# Sunsensors_v1_0.net
KiCad netlist of a schematic drawn in EAGLE
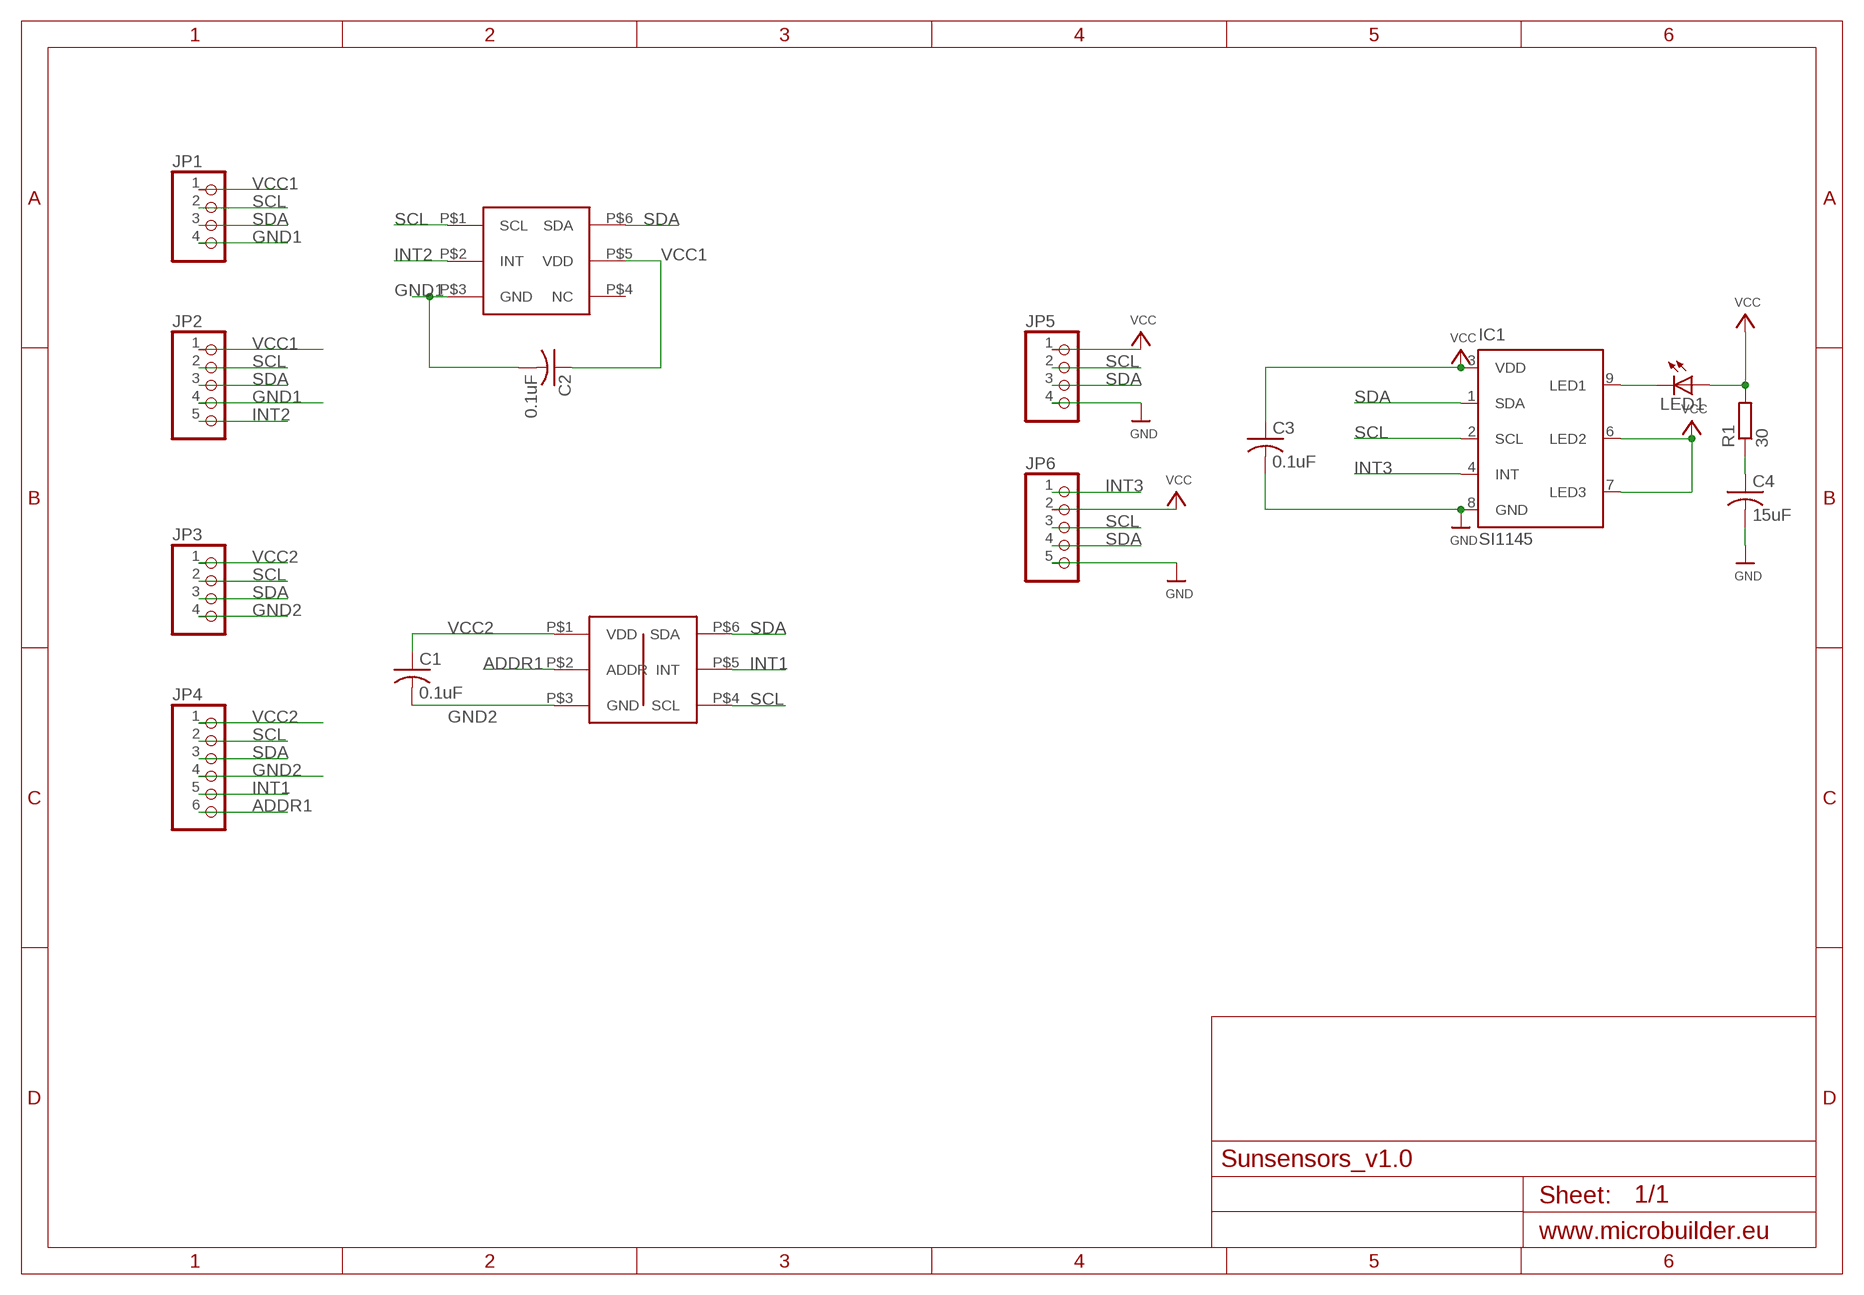
[diagram p0: schematic, sheet 1]

(export (version "E")
  (design (tool "Eeschema 10.0.6"))
  (components
    (comp (ref "C1")
      (value "0.1uF")
      (footprint "eagle-import:C0805")
      (libsource (lib "eagle-import") (part "C-USC0805"))
    )
    (comp (ref "C2")
      (value "0.1uF")
      (footprint "eagle-import:C0805")
      (libsource (lib "eagle-import") (part "C-USC0805"))
    )
    (comp (ref "C3")
      (value "0.1uF")
      (footprint "eagle-import:C0805")
      (libsource (lib "eagle-import") (part "C-USC0805"))
    )
    (comp (ref "C4")
      (value "15uF")
      (footprint "eagle-import:C0805")
      (libsource (lib "eagle-import") (part "C-USC0805"))
    )
    (comp (ref "IC1")
      (value "SI1145")
      (footprint "eagle-import:QFN-10")
      (libsource (lib "eagle-import") (part "SI1145"))
    )
    (comp (ref "JP1")
      (value "PINHD-1X4")
      (footprint "eagle-import:1X04")
      (libsource (lib "eagle-import") (part "PINHD-1X4"))
    )
    (comp (ref "JP2")
      (value "PINHD-1X5")
      (footprint "eagle-import:1X05")
      (libsource (lib "eagle-import") (part "PINHD-1X5"))
    )
    (comp (ref "JP3")
      (value "PINHD-1X4")
      (footprint "eagle-import:1X04")
      (libsource (lib "eagle-import") (part "PINHD-1X4"))
    )
    (comp (ref "JP4")
      (value "PINHD-1X6")
      (footprint "eagle-import:1X06")
      (libsource (lib "eagle-import") (part "PINHD-1X6"))
    )
    (comp (ref "JP5")
      (value "PINHD-1X4")
      (footprint "eagle-import:1X04")
      (libsource (lib "eagle-import") (part "PINHD-1X4"))
    )
    (comp (ref "JP6")
      (value "PINHD-1X5")
      (footprint "eagle-import:1X05")
      (libsource (lib "eagle-import") (part "PINHD-1X5"))
    )
    (comp (ref "LED1")
      (value "LEDCHIPLED_0805")
      (footprint "eagle-import:CHIPLED_0805")
      (libsource (lib "eagle-import") (part "LEDCHIPLED_0805"))
    )
    (comp (ref "R1")
      (value "30")
      (footprint "eagle-import:R1206")
      (libsource (lib "eagle-import") (part "R-EU_R1206"))
    )
    (comp (ref "U$8")
      (value "TSL25911FN")
      (footprint "eagle-import:ODFN6")
      (libsource (lib "eagle-import") (part "TSL25911FN"))
    )
    (comp (ref "U$9")
      (value "TSL2561T")
      (footprint "eagle-import:TMB-6")
      (libsource (lib "eagle-import") (part "TSL2561T"))
    )
  )
  (nets
    (net (code "1") (name "/ADDR1") (class "Default")
      (node (ref "JP4") (pin "6") (pinfunction "6_6") (pintype "passive"))
      (node (ref "U$9") (pin "P$2") (pinfunction "ADDR_P$2") (pintype "bidirectional"))
    )
    (net (code "2") (name "/GND1") (class "Default")
      (node (ref "C2") (pin "2") (pinfunction "2_2") (pintype "passive"))
      (node (ref "JP1") (pin "4") (pinfunction "4_4") (pintype "passive"))
      (node (ref "JP2") (pin "4") (pinfunction "4_4") (pintype "passive"))
      (node (ref "U$8") (pin "P$3") (pinfunction "GND_P$3") (pintype "bidirectional"))
    )
    (net (code "3") (name "/GND2") (class "Default")
      (node (ref "C1") (pin "2") (pinfunction "2_2") (pintype "passive"))
      (node (ref "JP3") (pin "4") (pinfunction "4_4") (pintype "passive"))
      (node (ref "JP4") (pin "4") (pinfunction "4_4") (pintype "passive"))
      (node (ref "U$9") (pin "P$3") (pinfunction "GND_P$3") (pintype "bidirectional"))
    )
    (net (code "4") (name "/INT1") (class "Default")
      (node (ref "JP4") (pin "5") (pinfunction "5_5") (pintype "passive"))
      (node (ref "U$9") (pin "P$5") (pinfunction "INT_P$5") (pintype "bidirectional"))
    )
    (net (code "5") (name "/INT2") (class "Default")
      (node (ref "JP2") (pin "5") (pinfunction "5_5") (pintype "passive"))
      (node (ref "U$8") (pin "P$2") (pinfunction "INT_P$2") (pintype "bidirectional"))
    )
    (net (code "6") (name "/INT3") (class "Default")
      (node (ref "IC1") (pin "4") (pinfunction "INT_4") (pintype "open_collector"))
      (node (ref "JP6") (pin "1") (pinfunction "1_1") (pintype "passive"))
    )
    (net (code "7") (name "/SCL") (class "Default")
      (node (ref "IC1") (pin "2") (pinfunction "SCL_2") (pintype "input"))
      (node (ref "JP1") (pin "2") (pinfunction "2_2") (pintype "passive"))
      (node (ref "JP2") (pin "2") (pinfunction "2_2") (pintype "passive"))
      (node (ref "JP3") (pin "2") (pinfunction "2_2") (pintype "passive"))
      (node (ref "JP4") (pin "2") (pinfunction "2_2") (pintype "passive"))
      (node (ref "JP5") (pin "2") (pinfunction "2_2") (pintype "passive"))
      (node (ref "JP6") (pin "3") (pinfunction "3_3") (pintype "passive"))
      (node (ref "U$8") (pin "P$1") (pinfunction "SCL_P$1") (pintype "bidirectional"))
      (node (ref "U$9") (pin "P$4") (pinfunction "SCL_P$4") (pintype "bidirectional"))
    )
    (net (code "8") (name "/SDA") (class "Default")
      (node (ref "IC1") (pin "1") (pinfunction "SDA_1") (pintype "bidirectional"))
      (node (ref "JP1") (pin "3") (pinfunction "3_3") (pintype "passive"))
      (node (ref "JP2") (pin "3") (pinfunction "3_3") (pintype "passive"))
      (node (ref "JP3") (pin "3") (pinfunction "3_3") (pintype "passive"))
      (node (ref "JP4") (pin "3") (pinfunction "3_3") (pintype "passive"))
      (node (ref "JP5") (pin "3") (pinfunction "3_3") (pintype "passive"))
      (node (ref "JP6") (pin "4") (pinfunction "4_4") (pintype "passive"))
      (node (ref "U$8") (pin "P$6") (pinfunction "SDA_P$6") (pintype "bidirectional"))
      (node (ref "U$9") (pin "P$6") (pinfunction "SDA_P$6") (pintype "bidirectional"))
    )
    (net (code "9") (name "/VCC1") (class "Default")
      (node (ref "C2") (pin "1") (pinfunction "1_1") (pintype "passive"))
      (node (ref "JP1") (pin "1") (pinfunction "1_1") (pintype "passive"))
      (node (ref "JP2") (pin "1") (pinfunction "1_1") (pintype "passive"))
      (node (ref "U$8") (pin "P$5") (pinfunction "VDD_P$5") (pintype "bidirectional"))
    )
    (net (code "10") (name "/VCC2") (class "Default")
      (node (ref "C1") (pin "1") (pinfunction "1_1") (pintype "passive"))
      (node (ref "JP3") (pin "1") (pinfunction "1_1") (pintype "passive"))
      (node (ref "JP4") (pin "1") (pinfunction "1_1") (pintype "passive"))
      (node (ref "U$9") (pin "P$1") (pinfunction "VDD_P$1") (pintype "bidirectional"))
    )
    (net (code "11") (name "GND") (class "Default")
      (node (ref "C3") (pin "2") (pinfunction "2_2") (pintype "passive"))
      (node (ref "C4") (pin "2") (pinfunction "2_2") (pintype "passive"))
      (node (ref "IC1") (pin "8") (pinfunction "GND_8") (pintype "power_in"))
      (node (ref "JP5") (pin "4") (pinfunction "4_4") (pintype "passive"))
      (node (ref "JP6") (pin "5") (pinfunction "5_5") (pintype "passive"))
    )
    (net (code "12") (name "Net-(C4-Pad1)") (class "Default")
      (node (ref "C4") (pin "1") (pinfunction "1_1") (pintype "passive"))
      (node (ref "R1") (pin "1") (pinfunction "1_1") (pintype "passive"))
    )
    (net (code "13") (name "Net-(IC1-LED1)") (class "Default")
      (node (ref "IC1") (pin "9") (pinfunction "LED1_9") (pintype "output"))
      (node (ref "LED1") (pin "C") (pinfunction "C_C") (pintype "passive"))
    )
    (net (code "14") (name "VCC") (class "Default")
      (node (ref "C3") (pin "1") (pinfunction "1_1") (pintype "passive"))
      (node (ref "IC1") (pin "3") (pinfunction "VDD_3") (pintype "power_in"))
      (node (ref "IC1") (pin "6") (pinfunction "LED2_6") (pintype "output"))
      (node (ref "IC1") (pin "7") (pinfunction "LED3_7") (pintype "output"))
      (node (ref "JP5") (pin "1") (pinfunction "1_1") (pintype "passive"))
      (node (ref "JP6") (pin "2") (pinfunction "2_2") (pintype "passive"))
      (node (ref "LED1") (pin "A") (pinfunction "A_A") (pintype "passive"))
      (node (ref "R1") (pin "2") (pinfunction "2_2") (pintype "passive"))
    )
    (net (code "15") (name "unconnected-(U$8-NC-PadP$4)") (class "Default")
      (node (ref "U$8") (pin "P$4") (pinfunction "NC_P$4") (pintype "bidirectional"))
    )
  )
)
